# interface-2-cart.net
KiCad netlist of a schematic drawn in EAGLE
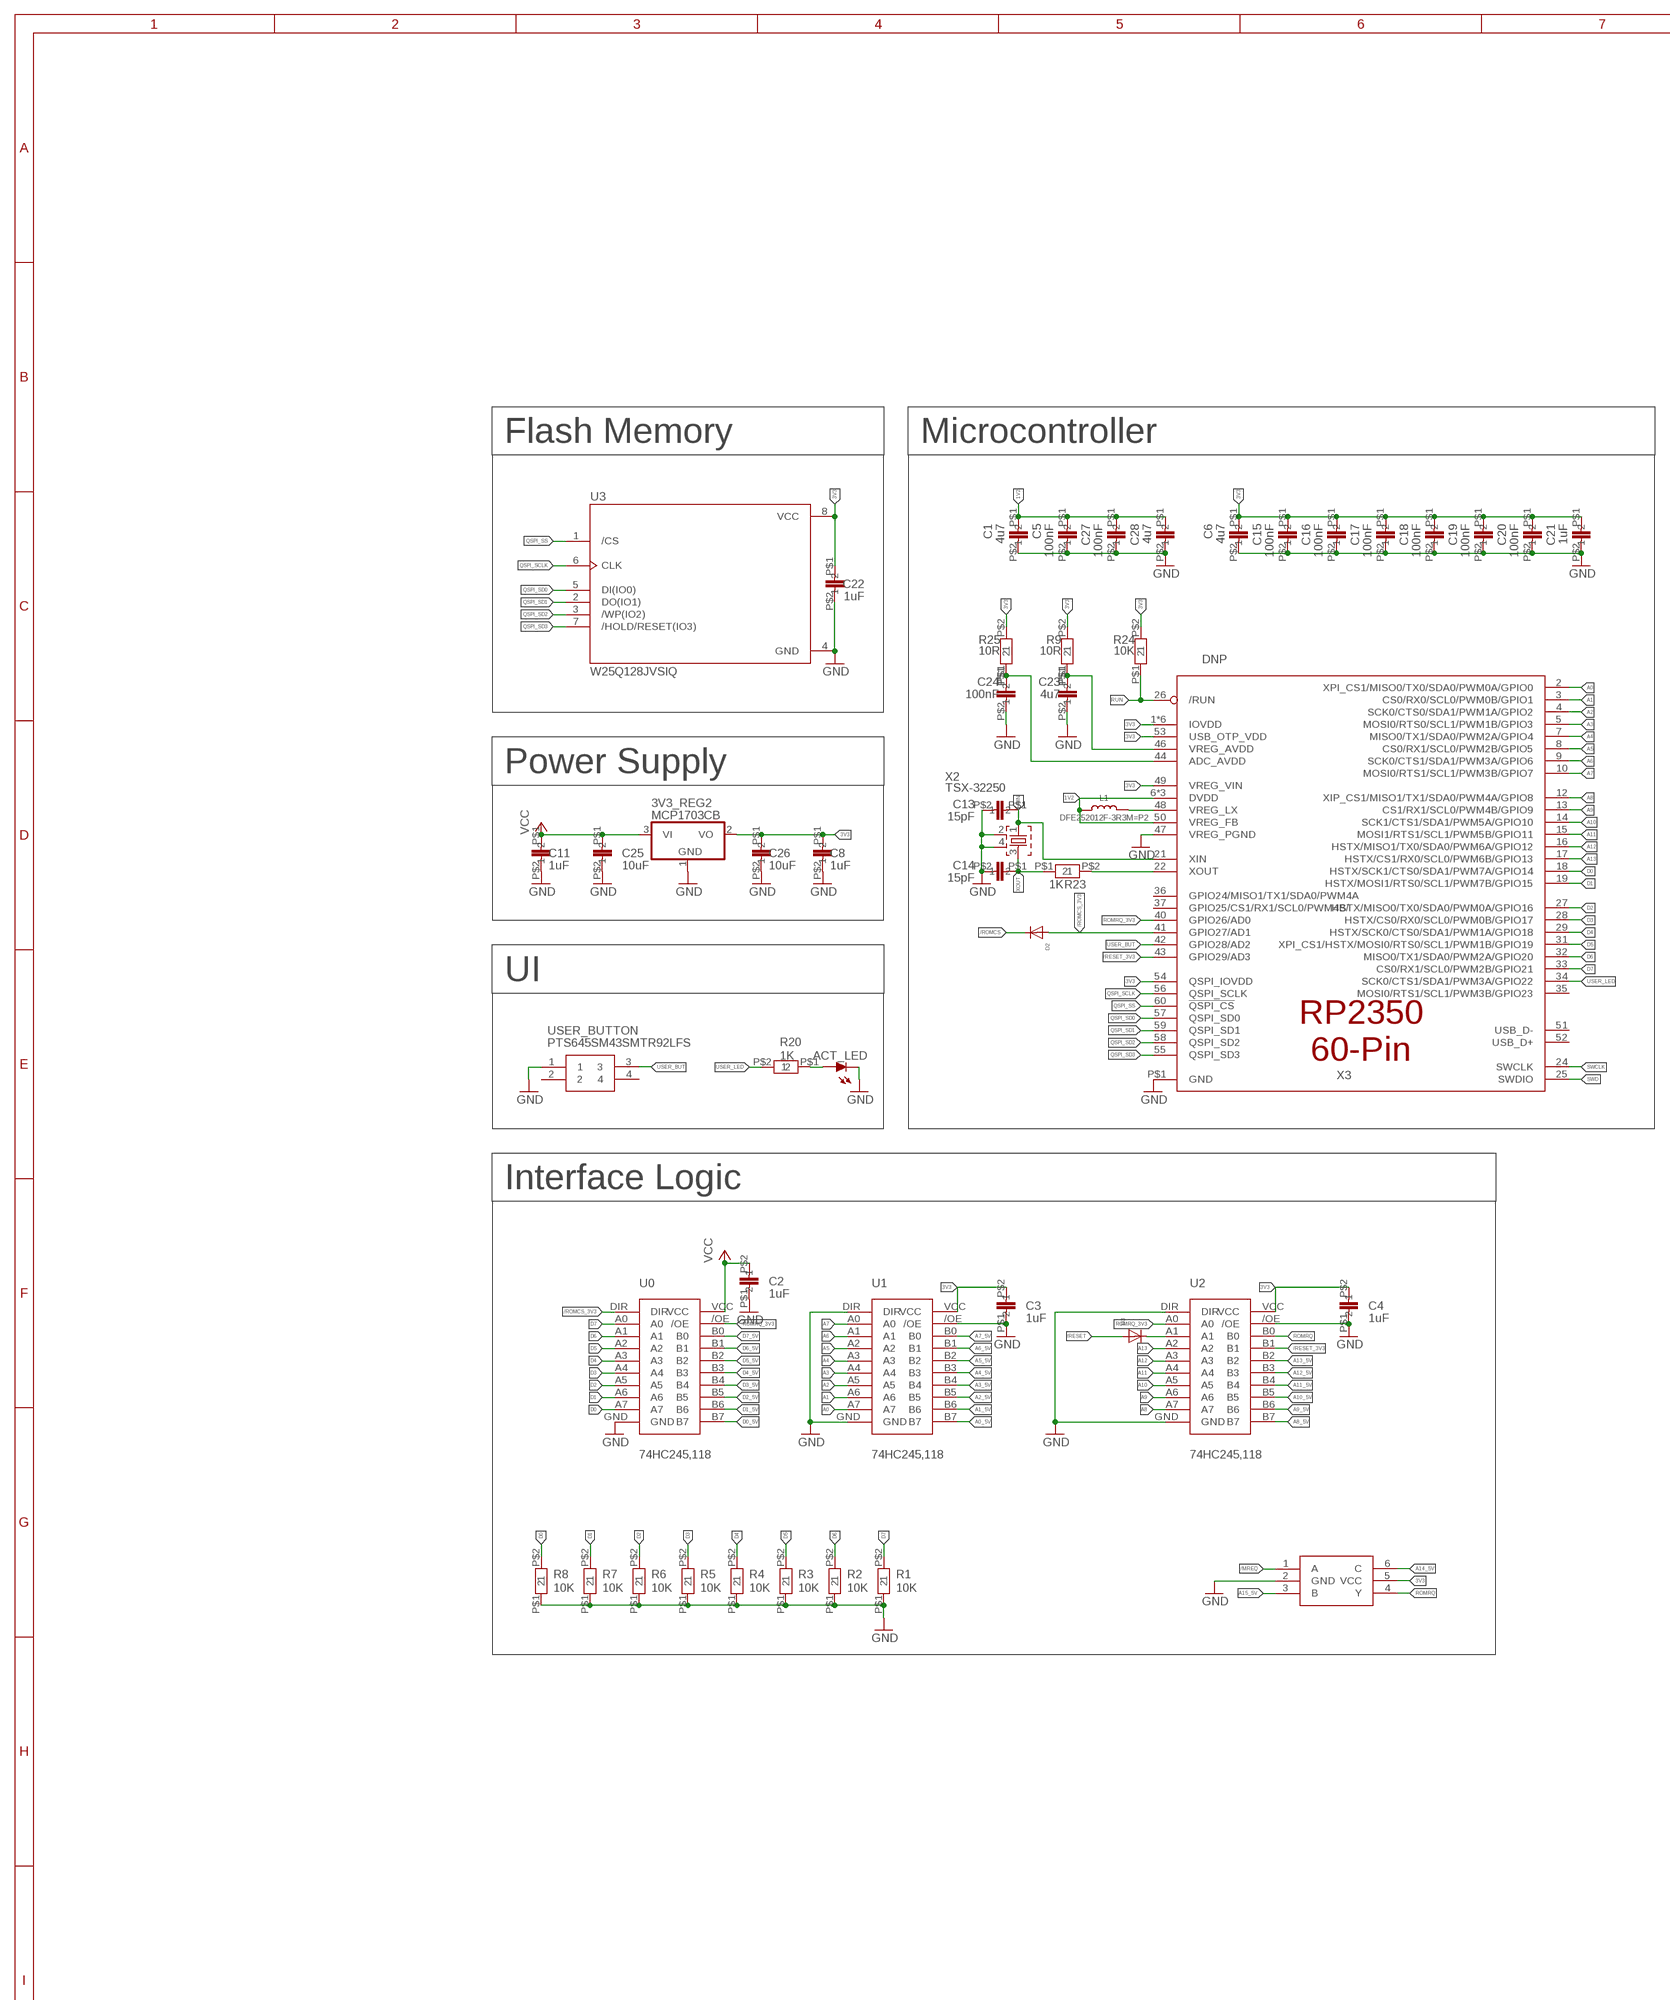
[diagram p0: schematic, sheet 1, part 1 of 2]
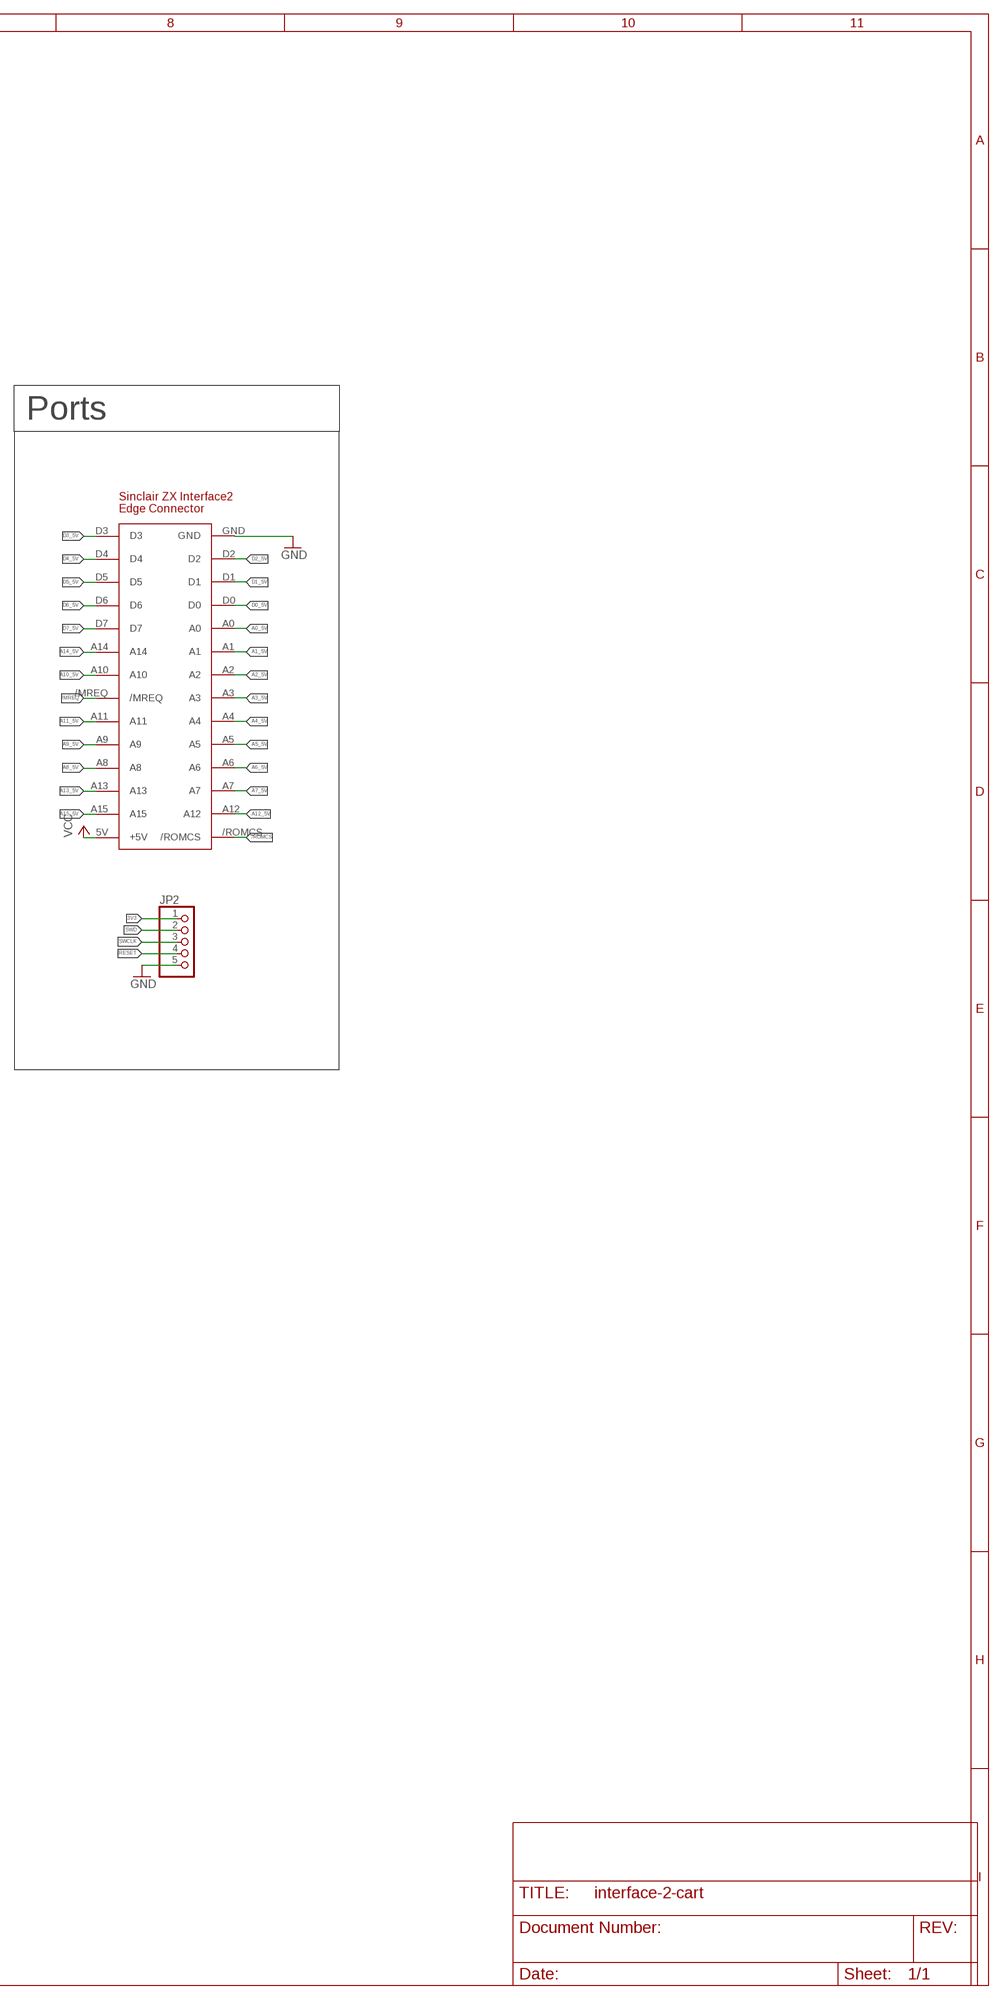
[diagram p1: schematic, sheet 1, part 2 of 2]

(export (version "E")
  (design (tool "Eeschema 10.0.6"))
  (components
    (comp (ref "3V3_REG2")
      (value "MCP1703CB")
      (footprint "eagle-import:SOT23")
      (libsource (lib "eagle-import") (part "MCP1703CB"))
    )
    (comp (ref "ACT_LED")
      (value "20mA")
      (footprint "eagle-import:LED_CHIP-LED0603MP")
      (libsource (lib "eagle-import") (part "LED_LEDCHIP-LED0603MP"))
    )
    (comp (ref "C1")
      (value "4u7")
      (footprint "eagle-import:C0402")
      (libsource (lib "eagle-import") (part "CAP-0402"))
    )
    (comp (ref "C2")
      (value "1uF")
      (footprint "eagle-import:C0402")
      (libsource (lib "eagle-import") (part "CAP-0402"))
    )
    (comp (ref "C3")
      (value "1uF")
      (footprint "eagle-import:C0402")
      (libsource (lib "eagle-import") (part "CAP-0402"))
    )
    (comp (ref "C4")
      (value "1uF")
      (footprint "eagle-import:C0402")
      (libsource (lib "eagle-import") (part "CAP-0402"))
    )
    (comp (ref "C5")
      (value "100nF")
      (footprint "eagle-import:C0402")
      (libsource (lib "eagle-import") (part "CAP-0402"))
    )
    (comp (ref "C6")
      (value "4u7")
      (footprint "eagle-import:C0402")
      (libsource (lib "eagle-import") (part "CAP-0402"))
    )
    (comp (ref "C8")
      (value "1uF")
      (footprint "eagle-import:C0402")
      (libsource (lib "eagle-import") (part "CAP-0402"))
    )
    (comp (ref "C11")
      (value "1uF")
      (footprint "eagle-import:C0402")
      (libsource (lib "eagle-import") (part "CAP-0402"))
    )
    (comp (ref "C13")
      (value "15pF")
      (footprint "eagle-import:C0402")
      (libsource (lib "eagle-import") (part "CAP-0402"))
    )
    (comp (ref "C14")
      (value "15pF")
      (footprint "eagle-import:C0402")
      (libsource (lib "eagle-import") (part "CAP-0402"))
    )
    (comp (ref "C15")
      (value "100nF")
      (footprint "eagle-import:C0402")
      (libsource (lib "eagle-import") (part "CAP-0402"))
    )
    (comp (ref "C16")
      (value "100nF")
      (footprint "eagle-import:C0402")
      (libsource (lib "eagle-import") (part "CAP-0402"))
    )
    (comp (ref "C17")
      (value "100nF")
      (footprint "eagle-import:C0402")
      (libsource (lib "eagle-import") (part "CAP-0402"))
    )
    (comp (ref "C18")
      (value "100nF")
      (footprint "eagle-import:C0402")
      (libsource (lib "eagle-import") (part "CAP-0402"))
    )
    (comp (ref "C19")
      (value "100nF")
      (footprint "eagle-import:C0402")
      (libsource (lib "eagle-import") (part "CAP-0402"))
    )
    (comp (ref "C20")
      (value "100nF")
      (footprint "eagle-import:C0402")
      (libsource (lib "eagle-import") (part "CAP-0402"))
    )
    (comp (ref "C21")
      (value "1uF")
      (footprint "eagle-import:C0402")
      (libsource (lib "eagle-import") (part "CAP-0402"))
    )
    (comp (ref "C22")
      (value "1uF")
      (footprint "eagle-import:C0402")
      (libsource (lib "eagle-import") (part "CAP-0402"))
    )
    (comp (ref "C23")
      (value "4u7")
      (footprint "eagle-import:C0402")
      (libsource (lib "eagle-import") (part "CAP-0402"))
    )
    (comp (ref "C24")
      (value "100nF")
      (footprint "eagle-import:C0402")
      (libsource (lib "eagle-import") (part "CAP-0402"))
    )
    (comp (ref "C25")
      (value "10uF")
      (footprint "eagle-import:C0402")
      (libsource (lib "eagle-import") (part "CAP-0402"))
    )
    (comp (ref "C26")
      (value "10uF")
      (footprint "eagle-import:C0402")
      (libsource (lib "eagle-import") (part "CAP-0402"))
    )
    (comp (ref "C27")
      (value "100nF")
      (footprint "eagle-import:C0402")
      (libsource (lib "eagle-import") (part "CAP-0402"))
    )
    (comp (ref "C28")
      (value "4u7")
      (footprint "eagle-import:C0402")
      (libsource (lib "eagle-import") (part "CAP-0402"))
    )
    (comp (ref "D2")
      (value "DIODESOD-323F")
      (footprint "eagle-import:SOD-323F")
      (libsource (lib "eagle-import") (part "DIODESOD-323F"))
    )
    (comp (ref "D3")
      (value "DIODESOD-323F")
      (footprint "eagle-import:SOD-323F")
      (libsource (lib "eagle-import") (part "DIODESOD-323F"))
    )
    (comp (ref "JP2")
      (value "PINHD-1X5")
      (footprint "eagle-import:1X05")
      (libsource (lib "eagle-import") (part "PINHD-1X5"))
    )
    (comp (ref "L1")
      (value "DFE252012F-3R3M=P2")
      (footprint "eagle-import:INDUCTOR_1007")
      (libsource (lib "eagle-import") (part "INDUCTOR"))
    )
    (comp (ref "R1")
      (value "10K")
      (footprint "eagle-import:0402")
      (libsource (lib "eagle-import") (part "RES-0402"))
    )
    (comp (ref "R2")
      (value "10K")
      (footprint "eagle-import:0402")
      (libsource (lib "eagle-import") (part "RES-0402"))
    )
    (comp (ref "R3")
      (value "10K")
      (footprint "eagle-import:0402")
      (libsource (lib "eagle-import") (part "RES-0402"))
    )
    (comp (ref "R4")
      (value "10K")
      (footprint "eagle-import:0402")
      (libsource (lib "eagle-import") (part "RES-0402"))
    )
    (comp (ref "R5")
      (value "10K")
      (footprint "eagle-import:0402")
      (libsource (lib "eagle-import") (part "RES-0402"))
    )
    (comp (ref "R6")
      (value "10K")
      (footprint "eagle-import:0402")
      (libsource (lib "eagle-import") (part "RES-0402"))
    )
    (comp (ref "R7")
      (value "10K")
      (footprint "eagle-import:0402")
      (libsource (lib "eagle-import") (part "RES-0402"))
    )
    (comp (ref "R8")
      (value "10K")
      (footprint "eagle-import:0402")
      (libsource (lib "eagle-import") (part "RES-0402"))
    )
    (comp (ref "R9")
      (value "10R")
      (footprint "eagle-import:0402")
      (libsource (lib "eagle-import") (part "RES-0402"))
    )
    (comp (ref "R20")
      (value "1K")
      (footprint "eagle-import:0402")
      (libsource (lib "eagle-import") (part "RES-0402"))
    )
    (comp (ref "R23")
      (value "1K")
      (footprint "eagle-import:0402")
      (libsource (lib "eagle-import") (part "RES-0402"))
    )
    (comp (ref "R24")
      (value "10K")
      (footprint "eagle-import:0402")
      (libsource (lib "eagle-import") (part "RES-0402"))
    )
    (comp (ref "R25")
      (value "10R")
      (footprint "eagle-import:0402")
      (libsource (lib "eagle-import") (part "RES-0402"))
    )
    (comp (ref "U$1")
      (value "ZX_I2_ROM_EDGE_CONNECTOR")
      (footprint "eagle-import:ZX_I2_ROM_EDGE_CONNECTOR_V2")
      (libsource (lib "eagle-import") (part "ZX_I2_ROM_EDGE_CONNECTOR"))
    )
    (comp (ref "U$2")
      (value "74LVC1G332GW,125")
      (footprint "eagle-import:SOP65P210X110-6N")
      (libsource (lib "eagle-import") (part "74LVC1G332GW,125"))
    )
    (comp (ref "U0")
      (value "SOP65P640X110-20N")
      (footprint "eagle-import:SOP65P640X110-20N")
      (fields (field (name "MANUFACTURER") "Nexperia USA"))
      (libsource (lib "eagle-import") (part "SOP65P640X110-20N"))
    )
    (comp (ref "U1")
      (value "SOP65P640X110-20N")
      (footprint "eagle-import:SOP65P640X110-20N")
      (fields (field (name "MANUFACTURER") "Nexperia USA"))
      (libsource (lib "eagle-import") (part "SOP65P640X110-20N"))
    )
    (comp (ref "U2")
      (value "SOP65P640X110-20N")
      (footprint "eagle-import:SOP65P640X110-20N")
      (fields (field (name "MANUFACTURER") "Nexperia USA"))
      (libsource (lib "eagle-import") (part "SOP65P640X110-20N"))
    )
    (comp (ref "U3")
      (value "W25Q128JVSIQ")
      (footprint "eagle-import:SOIC127P790X216-8N")
      (fields (field (name "MF") "Winbond Electronics"))
      (libsource (lib "eagle-import") (part "W25Q128JVSIQ"))
    )
    (comp (ref "USER_BUTTON")
      (value "PTS645SM43SMTR92LFS")
      (footprint "eagle-import:PTS645(SMT)")
      (fields (field (name "MOUSER_PART_NUMBER") "611-PTS645SM43SMTR92"))
      (libsource (lib "eagle-import") (part "PTS645SM43SMTR92LFS"))
    )
    (comp (ref "X2")
      (value "TSX-32250")
      (footprint "eagle-import:TSX-3225")
      (fields (field (name "MF") "EPSON") (field (name "MP") "TSX-3225"))
      (libsource (lib "eagle-import") (part "TSX-32250"))
    )
    (comp (ref "X3")
      (value "DNP")
      (footprint "eagle-import:QFN60_7MM_REDUCEDEPAD")
      (libsource (lib "eagle-import") (part "RP2350_QFN60"))
    )
  )
  (nets
    (net (code "1") (name "1V2") (class "Default")
      (node (ref "C1") (pin "P$1") (pinfunction "1_P$1") (pintype "passive"))
      (node (ref "C27") (pin "P$1") (pinfunction "1_P$1") (pintype "passive"))
      (node (ref "C28") (pin "P$1") (pinfunction "1_P$1") (pintype "passive"))
      (node (ref "C5") (pin "P$1") (pinfunction "1_P$1") (pintype "passive"))
      (node (ref "L1") (pin "P$1") (pinfunction "1_P$1") (pintype "passive"))
      (node (ref "X3") (pin "23") (pinfunction "DVDD_23") (pintype "power_in"))
      (node (ref "X3") (pin "39") (pinfunction "DVDD_39") (pintype "power_in"))
      (node (ref "X3") (pin "50") (pinfunction "VREG_FB_50") (pintype "input"))
      (node (ref "X3") (pin "6") (pinfunction "DVDD_6") (pintype "power_in"))
    )
    (net (code "2") (name "3V3") (class "Default")
      (node (ref "3V3_REG2") (pin "2") (pinfunction "VO_2") (pintype "passive"))
      (node (ref "C15") (pin "P$1") (pinfunction "1_P$1") (pintype "passive"))
      (node (ref "C16") (pin "P$1") (pinfunction "1_P$1") (pintype "passive"))
      (node (ref "C17") (pin "P$1") (pinfunction "1_P$1") (pintype "passive"))
      (node (ref "C18") (pin "P$1") (pinfunction "1_P$1") (pintype "passive"))
      (node (ref "C19") (pin "P$1") (pinfunction "1_P$1") (pintype "passive"))
      (node (ref "C20") (pin "P$1") (pinfunction "1_P$1") (pintype "passive"))
      (node (ref "C21") (pin "P$1") (pinfunction "1_P$1") (pintype "passive"))
      (node (ref "C22") (pin "P$1") (pinfunction "1_P$1") (pintype "passive"))
      (node (ref "C26") (pin "P$1") (pinfunction "1_P$1") (pintype "passive"))
      (node (ref "C3") (pin "P$2") (pinfunction "2_P$2") (pintype "passive"))
      (node (ref "C4") (pin "P$2") (pinfunction "2_P$2") (pintype "passive"))
      (node (ref "C6") (pin "P$1") (pinfunction "1_P$1") (pintype "passive"))
      (node (ref "C8") (pin "P$1") (pinfunction "1_P$1") (pintype "passive"))
      (node (ref "JP2") (pin "1") (pinfunction "1_1") (pintype "passive"))
      (node (ref "R24") (pin "P$2") (pinfunction "2_P$2") (pintype "passive"))
      (node (ref "R25") (pin "P$2") (pinfunction "2_P$2") (pintype "passive"))
      (node (ref "R9") (pin "P$2") (pinfunction "2_P$2") (pintype "passive"))
      (node (ref "U$2") (pin "5") (pinfunction "VCC_5") (pintype "bidirectional"))
      (node (ref "U1") (pin "VCC") (pinfunction "VCC_VCC") (pintype "power_in"))
      (node (ref "U2") (pin "VCC") (pinfunction "VCC_VCC") (pintype "power_in"))
      (node (ref "U3") (pin "8") (pinfunction "VCC_8") (pintype "power_in"))
      (node (ref "X3") (pin "1") (pinfunction "IOVDD_1") (pintype "power_in"))
      (node (ref "X3") (pin "11") (pinfunction "IOVDD_11") (pintype "power_in"))
      (node (ref "X3") (pin "20") (pinfunction "IOVDD_20") (pintype "power_in"))
      (node (ref "X3") (pin "30") (pinfunction "IOVDD_30") (pintype "power_in"))
      (node (ref "X3") (pin "38") (pinfunction "IOVDD_38") (pintype "power_in"))
      (node (ref "X3") (pin "45") (pinfunction "IOVDD_45") (pintype "power_in"))
      (node (ref "X3") (pin "49") (pinfunction "VREG_VIN_49") (pintype "input"))
      (node (ref "X3") (pin "53") (pinfunction "USB_OTP_VDD_53") (pintype "power_in"))
      (node (ref "X3") (pin "54") (pinfunction "QSPI_IOVDD_54") (pintype "power_in"))
    )
    (net (code "3") (name "A0") (class "Default")
      (node (ref "U1") (pin "A7") (pinfunction "A7_A7") (pintype "bidirectional"))
      (node (ref "X3") (pin "2") (pinfunction "XPI_CS1/MISO0/TX0/SDA0/PWM0A/GPIO0_2") (pintype "bidirectional"))
    )
    (net (code "4") (name "A0_5V") (class "Default")
      (node (ref "U$1") (pin "A0") (pinfunction "A0_A0") (pintype "bidirectional"))
      (node (ref "U1") (pin "B7") (pinfunction "B7_B7") (pintype "bidirectional"))
    )
    (net (code "5") (name "A1") (class "Default")
      (node (ref "U1") (pin "A6") (pinfunction "A6_A6") (pintype "bidirectional"))
      (node (ref "X3") (pin "3") (pinfunction "CS0/RX0/SCL0/PWM0B/GPIO1_3") (pintype "bidirectional"))
    )
    (net (code "6") (name "A1_5V") (class "Default")
      (node (ref "U$1") (pin "A1") (pinfunction "A1_A1") (pintype "bidirectional"))
      (node (ref "U1") (pin "B6") (pinfunction "B6_B6") (pintype "bidirectional"))
    )
    (net (code "7") (name "A2") (class "Default")
      (node (ref "U1") (pin "A5") (pinfunction "A5_A5") (pintype "bidirectional"))
      (node (ref "X3") (pin "4") (pinfunction "SCK0/CTS0/SDA1/PWM1A/GPIO2_4") (pintype "bidirectional"))
    )
    (net (code "8") (name "A2_5V") (class "Default")
      (node (ref "U$1") (pin "A2") (pinfunction "A2_A2") (pintype "bidirectional"))
      (node (ref "U1") (pin "B5") (pinfunction "B5_B5") (pintype "bidirectional"))
    )
    (net (code "9") (name "A3") (class "Default")
      (node (ref "U1") (pin "A4") (pinfunction "A4_A4") (pintype "bidirectional"))
      (node (ref "X3") (pin "5") (pinfunction "MOSI0/RTS0/SCL1/PWM1B/GPIO3_5") (pintype "bidirectional"))
    )
    (net (code "10") (name "A3_5V") (class "Default")
      (node (ref "U$1") (pin "A3") (pinfunction "A3_A3") (pintype "bidirectional"))
      (node (ref "U1") (pin "B4") (pinfunction "B4_B4") (pintype "bidirectional"))
    )
    (net (code "11") (name "A4") (class "Default")
      (node (ref "U1") (pin "A3") (pinfunction "A3_A3") (pintype "bidirectional"))
      (node (ref "X3") (pin "7") (pinfunction "MISO0/TX1/SDA0/PWM2A/GPIO4_7") (pintype "bidirectional"))
    )
    (net (code "12") (name "A4_5V") (class "Default")
      (node (ref "U$1") (pin "A4") (pinfunction "A4_A4") (pintype "bidirectional"))
      (node (ref "U1") (pin "B3") (pinfunction "B3_B3") (pintype "bidirectional"))
    )
    (net (code "13") (name "A5") (class "Default")
      (node (ref "U1") (pin "A2") (pinfunction "A2_A2") (pintype "bidirectional"))
      (node (ref "X3") (pin "8") (pinfunction "CS0/RX1/SCL0/PWM2B/GPIO5_8") (pintype "bidirectional"))
    )
    (net (code "14") (name "A5_5V") (class "Default")
      (node (ref "U$1") (pin "A5") (pinfunction "A5_A5") (pintype "bidirectional"))
      (node (ref "U1") (pin "B2") (pinfunction "B2_B2") (pintype "bidirectional"))
    )
    (net (code "15") (name "A6") (class "Default")
      (node (ref "U1") (pin "A1") (pinfunction "A1_A1") (pintype "bidirectional"))
      (node (ref "X3") (pin "9") (pinfunction "SCK0/CTS1/SDA1/PWM3A/GPIO6_9") (pintype "bidirectional"))
    )
    (net (code "16") (name "A6_5V") (class "Default")
      (node (ref "U$1") (pin "A6") (pinfunction "A6_A6") (pintype "bidirectional"))
      (node (ref "U1") (pin "B1") (pinfunction "B1_B1") (pintype "bidirectional"))
    )
    (net (code "17") (name "A7") (class "Default")
      (node (ref "U1") (pin "A0") (pinfunction "A0_A0") (pintype "bidirectional"))
      (node (ref "X3") (pin "10") (pinfunction "MOSI0/RTS1/SCL1/PWM3B/GPIO7_10") (pintype "bidirectional"))
    )
    (net (code "18") (name "A7_5V") (class "Default")
      (node (ref "U$1") (pin "A7") (pinfunction "A7_A7") (pintype "bidirectional"))
      (node (ref "U1") (pin "B0") (pinfunction "B0_B0") (pintype "bidirectional"))
    )
    (net (code "19") (name "A8") (class "Default")
      (node (ref "U2") (pin "A7") (pinfunction "A7_A7") (pintype "bidirectional"))
      (node (ref "X3") (pin "12") (pinfunction "XIP_CS1/MISO1/TX1/SDA0/PWM4A/GPIO8_12") (pintype "bidirectional"))
    )
    (net (code "20") (name "A8_5V") (class "Default")
      (node (ref "U$1") (pin "A8") (pinfunction "A8_A8") (pintype "bidirectional"))
      (node (ref "U2") (pin "B7") (pinfunction "B7_B7") (pintype "bidirectional"))
    )
    (net (code "21") (name "A9") (class "Default")
      (node (ref "U2") (pin "A6") (pinfunction "A6_A6") (pintype "bidirectional"))
      (node (ref "X3") (pin "13") (pinfunction "CS1/RX1/SCL0/PWM4B/GPIO9_13") (pintype "bidirectional"))
    )
    (net (code "22") (name "A9_5V") (class "Default")
      (node (ref "U$1") (pin "A9") (pinfunction "A9_A9") (pintype "bidirectional"))
      (node (ref "U2") (pin "B6") (pinfunction "B6_B6") (pintype "bidirectional"))
    )
    (net (code "23") (name "A10") (class "Default")
      (node (ref "U2") (pin "A5") (pinfunction "A5_A5") (pintype "bidirectional"))
      (node (ref "X3") (pin "14") (pinfunction "SCK1/CTS1/SDA1/PWM5A/GPIO10_14") (pintype "bidirectional"))
    )
    (net (code "24") (name "A10_5V") (class "Default")
      (node (ref "U$1") (pin "A10") (pinfunction "A10_A10") (pintype "bidirectional"))
      (node (ref "U2") (pin "B5") (pinfunction "B5_B5") (pintype "bidirectional"))
    )
    (net (code "25") (name "A11") (class "Default")
      (node (ref "U2") (pin "A4") (pinfunction "A4_A4") (pintype "bidirectional"))
      (node (ref "X3") (pin "15") (pinfunction "MOSI1/RTS1/SCL1/PWM5B/GPIO11_15") (pintype "bidirectional"))
    )
    (net (code "26") (name "A11_5V") (class "Default")
      (node (ref "U$1") (pin "A11") (pinfunction "A11_A11") (pintype "bidirectional"))
      (node (ref "U2") (pin "B4") (pinfunction "B4_B4") (pintype "bidirectional"))
    )
    (net (code "27") (name "A12") (class "Default")
      (node (ref "U2") (pin "A3") (pinfunction "A3_A3") (pintype "bidirectional"))
      (node (ref "X3") (pin "16") (pinfunction "HSTX/MISO1/TX0/SDA0/PWM6A/GPIO12_16") (pintype "bidirectional"))
    )
    (net (code "28") (name "A12_5V") (class "Default")
      (node (ref "U$1") (pin "A12") (pinfunction "A12_A12") (pintype "bidirectional"))
      (node (ref "U2") (pin "B3") (pinfunction "B3_B3") (pintype "bidirectional"))
    )
    (net (code "29") (name "A13") (class "Default")
      (node (ref "U2") (pin "A2") (pinfunction "A2_A2") (pintype "bidirectional"))
      (node (ref "X3") (pin "17") (pinfunction "HSTX/CS1/RX0/SCL0/PWM6B/GPIO13_17") (pintype "bidirectional"))
    )
    (net (code "30") (name "A13_5V") (class "Default")
      (node (ref "U$1") (pin "A13") (pinfunction "A13_A13") (pintype "bidirectional"))
      (node (ref "U2") (pin "B2") (pinfunction "B2_B2") (pintype "bidirectional"))
    )
    (net (code "31") (name "A14_5V") (class "Default")
      (node (ref "U$1") (pin "A14") (pinfunction "A14_A14") (pintype "bidirectional"))
      (node (ref "U$2") (pin "6") (pinfunction "C_6") (pintype "bidirectional"))
    )
    (net (code "32") (name "A15_5V") (class "Default")
      (node (ref "U$1") (pin "A15") (pinfunction "A15_A15") (pintype "bidirectional"))
      (node (ref "U$2") (pin "3") (pinfunction "B_3") (pintype "bidirectional"))
    )
    (net (code "33") (name "D0") (class "Default")
      (node (ref "R8") (pin "P$2") (pinfunction "2_P$2") (pintype "passive"))
      (node (ref "U0") (pin "A7") (pinfunction "A7_A7") (pintype "bidirectional"))
      (node (ref "X3") (pin "18") (pinfunction "HSTX/SCK1/CTS0/SDA1/PWM7A/GPIO14_18") (pintype "bidirectional"))
    )
    (net (code "34") (name "D0_5V") (class "Default")
      (node (ref "U$1") (pin "D0") (pinfunction "D0_D0") (pintype "bidirectional"))
      (node (ref "U0") (pin "B7") (pinfunction "B7_B7") (pintype "bidirectional"))
    )
    (net (code "35") (name "D1") (class "Default")
      (node (ref "R7") (pin "P$2") (pinfunction "2_P$2") (pintype "passive"))
      (node (ref "U0") (pin "A6") (pinfunction "A6_A6") (pintype "bidirectional"))
      (node (ref "X3") (pin "19") (pinfunction "HSTX/MOSI1/RTS0/SCL1/PWM7B/GPIO15_19") (pintype "bidirectional"))
    )
    (net (code "36") (name "D1_5V") (class "Default")
      (node (ref "U$1") (pin "D1") (pinfunction "D1_D1") (pintype "bidirectional"))
      (node (ref "U0") (pin "B6") (pinfunction "B6_B6") (pintype "bidirectional"))
    )
    (net (code "37") (name "D2") (class "Default")
      (node (ref "R6") (pin "P$2") (pinfunction "2_P$2") (pintype "passive"))
      (node (ref "U0") (pin "A5") (pinfunction "A5_A5") (pintype "bidirectional"))
      (node (ref "X3") (pin "27") (pinfunction "HSTX/MISO0/TX0/SDA0/PWM0A/GPIO16_27") (pintype "bidirectional"))
    )
    (net (code "38") (name "D2_5V") (class "Default")
      (node (ref "U$1") (pin "D2") (pinfunction "D2_D2") (pintype "bidirectional"))
      (node (ref "U0") (pin "B5") (pinfunction "B5_B5") (pintype "bidirectional"))
    )
    (net (code "39") (name "D3") (class "Default")
      (node (ref "R5") (pin "P$2") (pinfunction "2_P$2") (pintype "passive"))
      (node (ref "U0") (pin "A4") (pinfunction "A4_A4") (pintype "bidirectional"))
      (node (ref "X3") (pin "28") (pinfunction "HSTX/CS0/RX0/SCL0/PWM0B/GPIO17_28") (pintype "bidirectional"))
    )
    (net (code "40") (name "D3_5V") (class "Default")
      (node (ref "U$1") (pin "D3") (pinfunction "D3_D3") (pintype "bidirectional"))
      (node (ref "U0") (pin "B4") (pinfunction "B4_B4") (pintype "bidirectional"))
    )
    (net (code "41") (name "D4") (class "Default")
      (node (ref "R4") (pin "P$2") (pinfunction "2_P$2") (pintype "passive"))
      (node (ref "U0") (pin "A3") (pinfunction "A3_A3") (pintype "bidirectional"))
      (node (ref "X3") (pin "29") (pinfunction "HSTX/SCK0/CTS0/SDA1/PWM1A/GPIO18_29") (pintype "bidirectional"))
    )
    (net (code "42") (name "D4_5V") (class "Default")
      (node (ref "U$1") (pin "D4") (pinfunction "D4_D4") (pintype "bidirectional"))
      (node (ref "U0") (pin "B3") (pinfunction "B3_B3") (pintype "bidirectional"))
    )
    (net (code "43") (name "D5") (class "Default")
      (node (ref "R3") (pin "P$2") (pinfunction "2_P$2") (pintype "passive"))
      (node (ref "U0") (pin "A2") (pinfunction "A2_A2") (pintype "bidirectional"))
      (node (ref "X3") (pin "31") (pinfunction "XPI_CS1/HSTX/MOSI0/RTS0/SCL1/PWM1B/GPIO19_31") (pintype "bidirectional"))
    )
    (net (code "44") (name "D5_5V") (class "Default")
      (node (ref "U$1") (pin "D5") (pinfunction "D5_D5") (pintype "bidirectional"))
      (node (ref "U0") (pin "B2") (pinfunction "B2_B2") (pintype "bidirectional"))
    )
    (net (code "45") (name "D6") (class "Default")
      (node (ref "R2") (pin "P$2") (pinfunction "2_P$2") (pintype "passive"))
      (node (ref "U0") (pin "A1") (pinfunction "A1_A1") (pintype "bidirectional"))
      (node (ref "X3") (pin "32") (pinfunction "MISO0/TX1/SDA0/PWM2A/GPIO20_32") (pintype "bidirectional"))
    )
    (net (code "46") (name "D6_5V") (class "Default")
      (node (ref "U$1") (pin "D6") (pinfunction "D6_D6") (pintype "bidirectional"))
      (node (ref "U0") (pin "B1") (pinfunction "B1_B1") (pintype "bidirectional"))
    )
    (net (code "47") (name "D7") (class "Default")
      (node (ref "R1") (pin "P$2") (pinfunction "2_P$2") (pintype "passive"))
      (node (ref "U0") (pin "A0") (pinfunction "A0_A0") (pintype "bidirectional"))
      (node (ref "X3") (pin "33") (pinfunction "CS0/RX1/SCL0/PWM2B/GPIO21_33") (pintype "bidirectional"))
    )
    (net (code "48") (name "D7_5V") (class "Default")
      (node (ref "U$1") (pin "D7") (pinfunction "D7_D7") (pintype "bidirectional"))
      (node (ref "U0") (pin "B0") (pinfunction "B0_B0") (pintype "bidirectional"))
    )
    (net (code "49") (name "GND") (class "Default")
      (node (ref "3V3_REG2") (pin "1") (pinfunction "GND_1") (pintype "passive"))
      (node (ref "ACT_LED") (pin "C") (pinfunction "C_C") (pintype "passive"))
      (node (ref "C1") (pin "P$2") (pinfunction "2_P$2") (pintype "passive"))
      (node (ref "C11") (pin "P$2") (pinfunction "2_P$2") (pintype "passive"))
      (node (ref "C13") (pin "P$2") (pinfunction "2_P$2") (pintype "passive"))
      (node (ref "C14") (pin "P$2") (pinfunction "2_P$2") (pintype "passive"))
      (node (ref "C15") (pin "P$2") (pinfunction "2_P$2") (pintype "passive"))
      (node (ref "C16") (pin "P$2") (pinfunction "2_P$2") (pintype "passive"))
      (node (ref "C17") (pin "P$2") (pinfunction "2_P$2") (pintype "passive"))
      (node (ref "C18") (pin "P$2") (pinfunction "2_P$2") (pintype "passive"))
      (node (ref "C19") (pin "P$2") (pinfunction "2_P$2") (pintype "passive"))
      (node (ref "C2") (pin "P$1") (pinfunction "1_P$1") (pintype "passive"))
      (node (ref "C20") (pin "P$2") (pinfunction "2_P$2") (pintype "passive"))
      (node (ref "C21") (pin "P$2") (pinfunction "2_P$2") (pintype "passive"))
      (node (ref "C22") (pin "P$2") (pinfunction "2_P$2") (pintype "passive"))
      (node (ref "C23") (pin "P$2") (pinfunction "2_P$2") (pintype "passive"))
      (node (ref "C24") (pin "P$2") (pinfunction "2_P$2") (pintype "passive"))
      (node (ref "C25") (pin "P$2") (pinfunction "2_P$2") (pintype "passive"))
      (node (ref "C26") (pin "P$2") (pinfunction "2_P$2") (pintype "passive"))
      (node (ref "C27") (pin "P$2") (pinfunction "2_P$2") (pintype "passive"))
      (node (ref "C28") (pin "P$2") (pinfunction "2_P$2") (pintype "passive"))
      (node (ref "C3") (pin "P$1") (pinfunction "1_P$1") (pintype "passive"))
      (node (ref "C4") (pin "P$1") (pinfunction "1_P$1") (pintype "passive"))
      (node (ref "C5") (pin "P$2") (pinfunction "2_P$2") (pintype "passive"))
      (node (ref "C6") (pin "P$2") (pinfunction "2_P$2") (pintype "passive"))
      (node (ref "C8") (pin "P$2") (pinfunction "2_P$2") (pintype "passive"))
      (node (ref "JP2") (pin "5") (pinfunction "5_5") (pintype "passive"))
      (node (ref "R1") (pin "P$1") (pinfunction "1_P$1") (pintype "passive"))
      (node (ref "R2") (pin "P$1") (pinfunction "1_P$1") (pintype "passive"))
      (node (ref "R3") (pin "P$1") (pinfunction "1_P$1") (pintype "passive"))
      (node (ref "R4") (pin "P$1") (pinfunction "1_P$1") (pintype "passive"))
      (node (ref "R5") (pin "P$1") (pinfunction "1_P$1") (pintype "passive"))
      (node (ref "R6") (pin "P$1") (pinfunction "1_P$1") (pintype "passive"))
      (node (ref "R7") (pin "P$1") (pinfunction "1_P$1") (pintype "passive"))
      (node (ref "R8") (pin "P$1") (pinfunction "1_P$1") (pintype "passive"))
      (node (ref "U$1") (pin "GND") (pinfunction "GND_GND") (pintype "bidirectional"))
      (node (ref "U$2") (pin "2") (pinfunction "GND_2") (pintype "bidirectional"))
      (node (ref "U0") (pin "GND") (pinfunction "GND_GND") (pintype "power_in"))
      (node (ref "U1") (pin "/OE") (pinfunction "/OE_/OE") (pintype "input"))
      (node (ref "U1") (pin "DIR") (pinfunction "DIR_DIR") (pintype "input"))
      (node (ref "U1") (pin "GND") (pinfunction "GND_GND") (pintype "power_in"))
      (node (ref "U2") (pin "/OE") (pinfunction "/OE_/OE") (pintype "input"))
      (node (ref "U2") (pin "DIR") (pinfunction "DIR_DIR") (pintype "input"))
      (node (ref "U2") (pin "GND") (pinfunction "GND_GND") (pintype "power_in"))
      (node (ref "U3") (pin "4") (pinfunction "GND_4") (pintype "power_in"))
      (node (ref "USER_BUTTON") (pin "1") (pinfunction "1_1") (pintype "bidirectional"))
      (node (ref "X2") (pin "2") (pinfunction "2_2") (pintype "passive"))
      (node (ref "X2") (pin "4") (pinfunction "4_4") (pintype "passive"))
      (node (ref "X3") (pin "47") (pinfunction "VREG_PGND_47") (pintype "power_in"))
      (node (ref "X3") (pin "P$1") (pinfunction "GND_P$1") (pintype "power_in"))
    )
    (net (code "50") (name "Net-(C23-1)") (class "Default")
      (node (ref "C23") (pin "P$1") (pinfunction "1_P$1") (pintype "passive"))
      (node (ref "R9") (pin "P$1") (pinfunction "1_P$1") (pintype "passive"))
      (node (ref "X3") (pin "46") (pinfunction "VREG_AVDD_46") (pintype "power_in"))
    )
    (net (code "51") (name "Net-(C24-1)") (class "Default")
      (node (ref "C24") (pin "P$1") (pinfunction "1_P$1") (pintype "passive"))
      (node (ref "R25") (pin "P$1") (pinfunction "1_P$1") (pintype "passive"))
      (node (ref "X3") (pin "44") (pinfunction "ADC_AVDD_44") (pintype "power_in"))
    )
    (net (code "52") (name "Net-(D3-PadC)") (class "Default")
      (node (ref "D3") (pin "C") (pinfunction "C_C") (pintype "passive"))
      (node (ref "U2") (pin "A1") (pinfunction "A1_A1") (pintype "bidirectional"))
    )
    (net (code "53") (name "Net-(L1-2)") (class "Default")
      (node (ref "L1") (pin "P$2") (pinfunction "2_P$2") (pintype "passive"))
      (node (ref "X3") (pin "48") (pinfunction "VREG_LX_48") (pintype "input"))
    )
    (net (code "54") (name "Net-(R20-1)") (class "Default")
      (node (ref "ACT_LED") (pin "A") (pinfunction "A_A") (pintype "passive"))
      (node (ref "R20") (pin "P$1") (pinfunction "1_P$1") (pintype "passive"))
    )
    (net (code "55") (name "Net-(R23-2)") (class "Default")
      (node (ref "R23") (pin "P$2") (pinfunction "2_P$2") (pintype "passive"))
      (node (ref "X3") (pin "22") (pinfunction "XOUT_22") (pintype "output"))
    )
    (net (code "56") (name "QSPI_SCLK") (class "Default")
      (node (ref "U3") (pin "6") (pinfunction "CLK_6") (pintype "input"))
      (node (ref "X3") (pin "56") (pinfunction "QSPI_SCLK_56") (pintype "bidirectional"))
    )
    (net (code "57") (name "QSPI_SD0") (class "Default")
      (node (ref "U3") (pin "5") (pinfunction "DI(IO0)_5") (pintype "bidirectional"))
      (node (ref "X3") (pin "57") (pinfunction "QSPI_SD0_57") (pintype "bidirectional"))
    )
    (net (code "58") (name "QSPI_SD1") (class "Default")
      (node (ref "U3") (pin "2") (pinfunction "DO(IO1)_2") (pintype "bidirectional"))
      (node (ref "X3") (pin "59") (pinfunction "QSPI_SD1_59") (pintype "bidirectional"))
    )
    (net (code "59") (name "QSPI_SD2") (class "Default")
      (node (ref "U3") (pin "3") (pinfunction "/WP(IO2)_3") (pintype "bidirectional"))
      (node (ref "X3") (pin "58") (pinfunction "QSPI_SD2_58") (pintype "bidirectional"))
    )
    (net (code "60") (name "QSPI_SD3") (class "Default")
      (node (ref "U3") (pin "7") (pinfunction "/HOLD/RESET(IO3)_7") (pintype "bidirectional"))
      (node (ref "X3") (pin "55") (pinfunction "QSPI_SD3_55") (pintype "bidirectional"))
    )
    (net (code "61") (name "QSPI_SS") (class "Default")
      (node (ref "U3") (pin "1") (pinfunction "/CS_1") (pintype "input"))
      (node (ref "X3") (pin "60") (pinfunction "~{QSPI_CS}_60") (pintype "bidirectional"))
    )
    (net (code "62") (name "ROMRQ") (class "Default")
      (node (ref "U$2") (pin "4") (pinfunction "Y_4") (pintype "bidirectional"))
      (node (ref "U2") (pin "B0") (pinfunction "B0_B0") (pintype "bidirectional"))
    )
    (net (code "63") (name "ROMRQ_3V3") (class "Default")
      (node (ref "U0") (pin "/OE") (pinfunction "/OE_/OE") (pintype "input"))
      (node (ref "U2") (pin "A0") (pinfunction "A0_A0") (pintype "bidirectional"))
      (node (ref "X3") (pin "40") (pinfunction "GPIO26/AD0_40") (pintype "bidirectional"))
    )
    (net (code "64") (name "RUN") (class "Default")
      (node (ref "R24") (pin "P$1") (pinfunction "1_P$1") (pintype "passive"))
      (node (ref "X3") (pin "26") (pinfunction "/RUN_26") (pintype "bidirectional"))
    )
    (net (code "65") (name "SWCLK") (class "Default")
      (node (ref "JP2") (pin "3") (pinfunction "3_3") (pintype "passive"))
      (node (ref "X3") (pin "24") (pinfunction "SWCLK_24") (pintype "bidirectional"))
    )
    (net (code "66") (name "SWD") (class "Default")
      (node (ref "JP2") (pin "2") (pinfunction "2_2") (pintype "passive"))
      (node (ref "X3") (pin "25") (pinfunction "SWDIO_25") (pintype "bidirectional"))
    )
    (net (code "67") (name "USER_BUT") (class "Default")
      (node (ref "USER_BUTTON") (pin "3") (pinfunction "3_3") (pintype "bidirectional"))
      (node (ref "X3") (pin "42") (pinfunction "GPIO28/AD2_42") (pintype "bidirectional"))
    )
    (net (code "68") (name "USER_LED") (class "Default")
      (node (ref "R20") (pin "P$2") (pinfunction "2_P$2") (pintype "passive"))
      (node (ref "X3") (pin "34") (pinfunction "SCK0/CTS1/SDA1/PWM3A/GPIO22_34") (pintype "bidirectional"))
    )
    (net (code "69") (name "VCC") (class "Default")
      (node (ref "3V3_REG2") (pin "3") (pinfunction "VI_3") (pintype "input"))
      (node (ref "C11") (pin "P$1") (pinfunction "1_P$1") (pintype "passive"))
      (node (ref "C2") (pin "P$2") (pinfunction "2_P$2") (pintype "passive"))
      (node (ref "C25") (pin "P$1") (pinfunction "1_P$1") (pintype "passive"))
      (node (ref "U$1") (pin "5V") (pinfunction "+5V_5V") (pintype "bidirectional"))
      (node (ref "U0") (pin "VCC") (pinfunction "VCC_VCC") (pintype "power_in"))
    )
    (net (code "70") (name "XIN") (class "Default")
      (node (ref "C13") (pin "P$1") (pinfunction "1_P$1") (pintype "passive"))
      (node (ref "X2") (pin "1") (pinfunction "1_1") (pintype "passive"))
      (node (ref "X3") (pin "21") (pinfunction "XIN_21") (pintype "input"))
    )
    (net (code "71") (name "XOUT") (class "Default")
      (node (ref "C14") (pin "P$1") (pinfunction "1_P$1") (pintype "passive"))
      (node (ref "R23") (pin "P$1") (pinfunction "1_P$1") (pintype "passive"))
      (node (ref "X2") (pin "3") (pinfunction "3_3") (pintype "passive"))
    )
    (net (code "72") (name "unconnected-(USER_BUTTON-Pad2)") (class "Default")
      (node (ref "USER_BUTTON") (pin "2") (pinfunction "2_2") (pintype "bidirectional"))
    )
    (net (code "73") (name "unconnected-(USER_BUTTON-Pad4)") (class "Default")
      (node (ref "USER_BUTTON") (pin "4") (pinfunction "4_4") (pintype "bidirectional"))
    )
    (net (code "74") (name "unconnected-(X3-GPIO24{slash}MISO1{slash}TX1{slash}SDA0{slash}PWM4A-Pad36)") (class "Default")
      (node (ref "X3") (pin "36") (pinfunction "GPIO24/MISO1/TX1/SDA0/PWM4A_36") (pintype "bidirectional"))
    )
    (net (code "75") (name "unconnected-(X3-GPIO25{slash}CS1{slash}RX1{slash}SCL0{slash}PWM4B{slash}-Pad37)") (class "Default")
      (node (ref "X3") (pin "37") (pinfunction "GPIO25/CS1/RX1/SCL0/PWM4B/_37") (pintype "bidirectional"))
    )
    (net (code "76") (name "unconnected-(X3-MOSI0{slash}RTS1{slash}SCL1{slash}PWM3B{slash}GPIO23-Pad35)") (class "Default")
      (node (ref "X3") (pin "35") (pinfunction "MOSI0/RTS1/SCL1/PWM3B/GPIO23_35") (pintype "bidirectional"))
    )
    (net (code "77") (name "unconnected-(X3-USB_D+-Pad52)") (class "Default")
      (node (ref "X3") (pin "52") (pinfunction "USB_D+_52") (pintype "bidirectional"))
    )
    (net (code "78") (name "unconnected-(X3-USB_D--Pad51)") (class "Default")
      (node (ref "X3") (pin "51") (pinfunction "USB_D-_51") (pintype "bidirectional"))
    )
    (net (code "79") (name "{slash}MREQ") (class "Default")
      (node (ref "U$1") (pin "/MREQ") (pinfunction "/MREQ_/MREQ") (pintype "bidirectional"))
      (node (ref "U$2") (pin "1") (pinfunction "A_1") (pintype "bidirectional"))
    )
    (net (code "80") (name "{slash}RESET") (class "Default")
      (node (ref "D3") (pin "A") (pinfunction "A_A") (pintype "passive"))
      (node (ref "JP2") (pin "4") (pinfunction "4_4") (pintype "passive"))
    )
    (net (code "81") (name "{slash}RESET_3V3") (class "Default")
      (node (ref "U2") (pin "B1") (pinfunction "B1_B1") (pintype "bidirectional"))
      (node (ref "X3") (pin "43") (pinfunction "GPIO29/AD3_43") (pintype "bidirectional"))
    )
    (net (code "82") (name "{slash}ROMCS") (class "Default")
      (node (ref "D2") (pin "C") (pinfunction "C_C") (pintype "passive"))
      (node (ref "U$1") (pin "/ROMCS") (pinfunction "/ROMCS_/ROMCS") (pintype "bidirectional"))
    )
    (net (code "83") (name "{slash}ROMCS_3V3") (class "Default")
      (node (ref "D2") (pin "A") (pinfunction "A_A") (pintype "passive"))
      (node (ref "U0") (pin "DIR") (pinfunction "DIR_DIR") (pintype "input"))
      (node (ref "X3") (pin "41") (pinfunction "GPIO27/AD1_41") (pintype "bidirectional"))
    )
  )
)
